# RespiroProject_v0_4.net
KiCad netlist of a schematic drawn in EAGLE
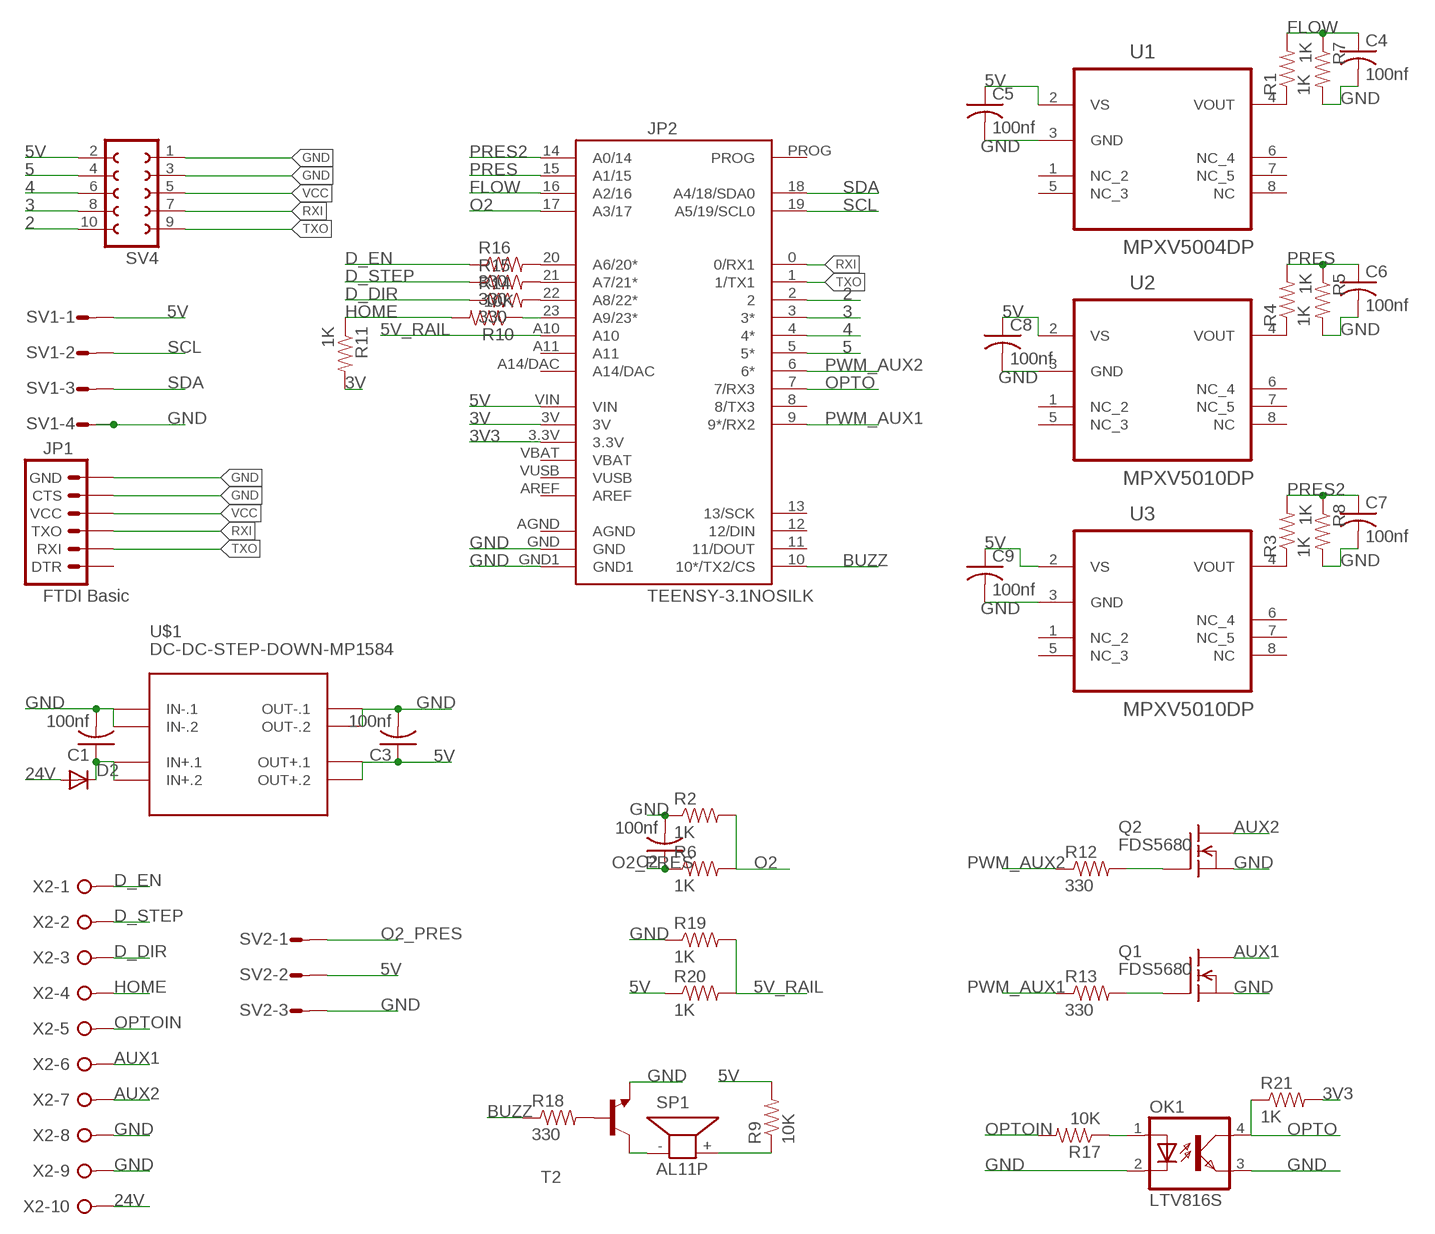
[diagram p0: schematic, sheet 1]

(export (version "E")
  (design (tool "Eeschema 10.0.6"))
  (components
    (comp (ref "C1")
      (value "100nf")
      (footprint "eagle-import:C0805")
      (libsource (lib "eagle-import") (part "C-USC0805"))
    )
    (comp (ref "C2")
      (value "100nf")
      (footprint "eagle-import:C0805")
      (libsource (lib "eagle-import") (part "C-USC0805"))
    )
    (comp (ref "C3")
      (value "100nf")
      (footprint "eagle-import:C0805")
      (libsource (lib "eagle-import") (part "C-USC0805"))
    )
    (comp (ref "C4")
      (value "100nf")
      (footprint "eagle-import:C0805")
      (libsource (lib "eagle-import") (part "C-USC0805"))
    )
    (comp (ref "C5")
      (value "100nf")
      (footprint "eagle-import:C0805")
      (libsource (lib "eagle-import") (part "C-USC0805"))
    )
    (comp (ref "C6")
      (value "100nf")
      (footprint "eagle-import:C0805")
      (libsource (lib "eagle-import") (part "C-USC0805"))
    )
    (comp (ref "C7")
      (value "100nf")
      (footprint "eagle-import:C0805")
      (libsource (lib "eagle-import") (part "C-USC0805"))
    )
    (comp (ref "C8")
      (value "100nf")
      (footprint "eagle-import:C0805")
      (libsource (lib "eagle-import") (part "C-USC0805"))
    )
    (comp (ref "C9")
      (value "100nf")
      (footprint "eagle-import:C0805")
      (libsource (lib "eagle-import") (part "C-USC0805"))
    )
    (comp (ref "D2")
      (value "DIODE-MINIMELF")
      (footprint "eagle-import:MINIMELF")
      (libsource (lib "eagle-import") (part "DIODE-MINIMELF"))
    )
    (comp (ref "JP1")
      (value "FTDI Basic")
      (footprint "eagle-import:1X06")
      (libsource (lib "eagle-import") (part "ARDUINO_SERIAL_PROGRAMPTH"))
    )
    (comp (ref "JP2")
      (value "TEENSY-3.1NOSILK")
      (footprint "eagle-import:TEENSY-3.1_NOSILK")
      (libsource (lib "eagle-import") (part "TEENSY-3.1NOSILK"))
    )
    (comp (ref "OK1")
      (value "LTV816S")
      (footprint "eagle-import:DIL4-SMD")
      (libsource (lib "eagle-import") (part "LTV816S"))
    )
    (comp (ref "Q1")
      (value "FDS5680")
      (footprint "eagle-import:SO-8")
      (libsource (lib "eagle-import") (part "FDS5680"))
    )
    (comp (ref "Q2")
      (value "FDS5680")
      (footprint "eagle-import:SO-8")
      (libsource (lib "eagle-import") (part "FDS5680"))
    )
    (comp (ref "R1")
      (value "1K")
      (footprint "eagle-import:0805")
      (libsource (lib "eagle-import") (part "RESISTOR0805-RES"))
    )
    (comp (ref "R2")
      (value "1K")
      (footprint "eagle-import:0805")
      (libsource (lib "eagle-import") (part "RESISTOR0805-RES"))
    )
    (comp (ref "R3")
      (value "1K")
      (footprint "eagle-import:0805")
      (libsource (lib "eagle-import") (part "RESISTOR0805-RES"))
    )
    (comp (ref "R4")
      (value "1K")
      (footprint "eagle-import:0805")
      (libsource (lib "eagle-import") (part "RESISTOR0805-RES"))
    )
    (comp (ref "R5")
      (value "1K")
      (footprint "eagle-import:0805")
      (libsource (lib "eagle-import") (part "RESISTOR0805-RES"))
    )
    (comp (ref "R6")
      (value "1K")
      (footprint "eagle-import:0805")
      (libsource (lib "eagle-import") (part "RESISTOR0805-RES"))
    )
    (comp (ref "R7")
      (value "1K")
      (footprint "eagle-import:0805")
      (libsource (lib "eagle-import") (part "RESISTOR0805-RES"))
    )
    (comp (ref "R8")
      (value "1K")
      (footprint "eagle-import:0805")
      (libsource (lib "eagle-import") (part "RESISTOR0805-RES"))
    )
    (comp (ref "R9")
      (value "10K")
      (footprint "eagle-import:0805")
      (libsource (lib "eagle-import") (part "RESISTOR0805-RES"))
    )
    (comp (ref "R10")
      (value "10K")
      (footprint "eagle-import:0805")
      (libsource (lib "eagle-import") (part "RESISTOR0805-RES"))
    )
    (comp (ref "R11")
      (value "1K")
      (footprint "eagle-import:0805")
      (libsource (lib "eagle-import") (part "RESISTOR0805-RES"))
    )
    (comp (ref "R12")
      (value "330")
      (footprint "eagle-import:0805")
      (libsource (lib "eagle-import") (part "RESISTOR0805-RES"))
    )
    (comp (ref "R13")
      (value "330")
      (footprint "eagle-import:0805")
      (libsource (lib "eagle-import") (part "RESISTOR0805-RES"))
    )
    (comp (ref "R14")
      (value "330")
      (footprint "eagle-import:0805")
      (libsource (lib "eagle-import") (part "RESISTOR0805-RES"))
    )
    (comp (ref "R15")
      (value "330")
      (footprint "eagle-import:0805")
      (libsource (lib "eagle-import") (part "RESISTOR0805-RES"))
    )
    (comp (ref "R16")
      (value "330")
      (footprint "eagle-import:0805")
      (libsource (lib "eagle-import") (part "RESISTOR0805-RES"))
    )
    (comp (ref "R17")
      (value "10K")
      (footprint "eagle-import:0805")
      (libsource (lib "eagle-import") (part "RESISTOR0805-RES"))
    )
    (comp (ref "R18")
      (value "330")
      (footprint "eagle-import:0805")
      (libsource (lib "eagle-import") (part "RESISTOR0805-RES"))
    )
    (comp (ref "R19")
      (value "1K")
      (footprint "eagle-import:0805")
      (libsource (lib "eagle-import") (part "RESISTOR0805-RES"))
    )
    (comp (ref "R20")
      (value "1K")
      (footprint "eagle-import:0805")
      (libsource (lib "eagle-import") (part "RESISTOR0805-RES"))
    )
    (comp (ref "R21")
      (value "1K")
      (footprint "eagle-import:0805")
      (libsource (lib "eagle-import") (part "RESISTOR0805-RES"))
    )
    (comp (ref "SP1")
      (value "AL11P")
      (footprint "eagle-import:AL11P")
      (libsource (lib "eagle-import") (part "AL11P"))
    )
    (comp (ref "SV1")
      (value "S04P")
      (footprint "eagle-import:S04P")
      (libsource (lib "eagle-import") (part "S04P"))
    )
    (comp (ref "SV2")
      (value "S03P")
      (footprint "eagle-import:S03P")
      (libsource (lib "eagle-import") (part "S03P"))
    )
    (comp (ref "SV4")
      (value "FE05-2")
      (footprint "eagle-import:FE05-2")
      (libsource (lib "eagle-import") (part "FE05-2"))
    )
    (comp (ref "T2")
      (value "BC817-16-NPN-SOT23-BEC")
      (footprint "eagle-import:SOT23-BEC")
      (libsource (lib "eagle-import") (part "-NPN-SOT23-BECBC817-16"))
    )
    (comp (ref "U$1")
      (value "DC-DC-STEP-DOWN-MP1584")
      (footprint "eagle-import:DC-DC-STEP-DOWN-MP1584")
      (libsource (lib "eagle-import") (part "DC-DC-STEP-DOWN-MP1584"))
    )
    (comp (ref "U1")
      (value "MPXV5004DP")
      (footprint "eagle-import:FREESCALE_CASE_1351-01")
      (libsource (lib "eagle-import") (part "MPXV5004DP"))
    )
    (comp (ref "U2")
      (value "MPXV5010DP")
      (footprint "eagle-import:FREESCALE_CASE_1351-01")
      (fields (field (name "MPN") "MPXV5004DP"))
      (libsource (lib "eagle-import") (part "MPXV5004DP"))
    )
    (comp (ref "U3")
      (value "MPXV5010DP")
      (footprint "eagle-import:FREESCALE_CASE_1351-01")
      (fields (field (name "MPN") "MPXV5004DP"))
      (libsource (lib "eagle-import") (part "MPXV5004DP"))
    )
    (comp (ref "X2")
      (value "W237-10P")
      (footprint "eagle-import:W237-10P")
      (libsource (lib "eagle-import") (part "W237-10P"))
    )
  )
  (nets
    (net (code "1") (name "/2") (class "Default")
      (node (ref "JP2") (pin "2") (pinfunction "2_2") (pintype "bidirectional"))
      (node (ref "SV4") (pin "10") (pinfunction "10_10") (pintype "passive"))
    )
    (net (code "2") (name "/3") (class "Default")
      (node (ref "JP2") (pin "3") (pinfunction "3*_3") (pintype "bidirectional"))
      (node (ref "SV4") (pin "8") (pinfunction "8_8") (pintype "passive"))
    )
    (net (code "3") (name "/3V") (class "Default")
      (node (ref "JP2") (pin "3V") (pinfunction "3V_3V") (pintype "bidirectional"))
      (node (ref "R11") (pin "2") (pinfunction "2_2") (pintype "passive"))
    )
    (net (code "4") (name "/3V3") (class "Default")
      (node (ref "JP2") (pin "3.3V") (pinfunction "3.3V_3.3V") (pintype "bidirectional"))
      (node (ref "R21") (pin "2") (pinfunction "2_2") (pintype "passive"))
    )
    (net (code "5") (name "/4") (class "Default")
      (node (ref "JP2") (pin "4") (pinfunction "4*_4") (pintype "bidirectional"))
      (node (ref "SV4") (pin "6") (pinfunction "6_6") (pintype "passive"))
    )
    (net (code "6") (name "/5") (class "Default")
      (node (ref "JP2") (pin "5") (pinfunction "5*_5") (pintype "bidirectional"))
      (node (ref "SV4") (pin "4") (pinfunction "4_4") (pintype "passive"))
    )
    (net (code "7") (name "/5V") (class "Default")
      (node (ref "C3") (pin "1") (pinfunction "1_1") (pintype "passive"))
      (node (ref "C5") (pin "1") (pinfunction "1_1") (pintype "passive"))
      (node (ref "C8") (pin "1") (pinfunction "1_1") (pintype "passive"))
      (node (ref "C9") (pin "1") (pinfunction "1_1") (pintype "passive"))
      (node (ref "JP2") (pin "VIN") (pinfunction "VIN_VIN") (pintype "bidirectional"))
      (node (ref "R20") (pin "1") (pinfunction "1_1") (pintype "passive"))
      (node (ref "R9") (pin "2") (pinfunction "2_2") (pintype "passive"))
      (node (ref "SV1") (pin "1") (pinfunction "S_1") (pintype "passive"))
      (node (ref "SV2") (pin "2") (pinfunction "S_2") (pintype "passive"))
      (node (ref "SV4") (pin "2") (pinfunction "2_2") (pintype "passive"))
      (node (ref "U$1") (pin "OUT+.1") (pinfunction "OUT+.1_OUT+.1") (pintype "bidirectional"))
      (node (ref "U$1") (pin "OUT+.2") (pinfunction "OUT+.2_OUT+.2") (pintype "bidirectional"))
      (node (ref "U1") (pin "2") (pinfunction "VS_2") (pintype "power_in"))
      (node (ref "U2") (pin "2") (pinfunction "VS_2") (pintype "power_in"))
      (node (ref "U3") (pin "2") (pinfunction "VS_2") (pintype "power_in"))
    )
    (net (code "8") (name "/5V_RAIL") (class "Default")
      (node (ref "JP2") (pin "A10") (pinfunction "A10_A10") (pintype "bidirectional"))
      (node (ref "R19") (pin "2") (pinfunction "2_2") (pintype "passive"))
      (node (ref "R20") (pin "2") (pinfunction "2_2") (pintype "passive"))
    )
    (net (code "9") (name "/24V") (class "Default")
      (node (ref "D2") (pin "A") (pinfunction "A_A") (pintype "passive"))
      (node (ref "X2") (pin "10") (pinfunction "KL_10") (pintype "passive"))
    )
    (net (code "10") (name "/AUX1") (class "Default")
      (node (ref "Q1") (pin "5") (pinfunction "D_5") (pintype "passive"))
      (node (ref "Q1") (pin "6") (pinfunction "D_6") (pintype "passive"))
      (node (ref "Q1") (pin "7") (pinfunction "D_7") (pintype "passive"))
      (node (ref "Q1") (pin "8") (pinfunction "D_8") (pintype "passive"))
      (node (ref "X2") (pin "6") (pinfunction "KL_6") (pintype "passive"))
    )
    (net (code "11") (name "/AUX2") (class "Default")
      (node (ref "Q2") (pin "5") (pinfunction "D_5") (pintype "passive"))
      (node (ref "Q2") (pin "6") (pinfunction "D_6") (pintype "passive"))
      (node (ref "Q2") (pin "7") (pinfunction "D_7") (pintype "passive"))
      (node (ref "Q2") (pin "8") (pinfunction "D_8") (pintype "passive"))
      (node (ref "X2") (pin "7") (pinfunction "KL_7") (pintype "passive"))
    )
    (net (code "12") (name "/BUZZ") (class "Default")
      (node (ref "JP2") (pin "10") (pinfunction "10*/TX2/CS_10") (pintype "bidirectional"))
      (node (ref "R18") (pin "1") (pinfunction "1_1") (pintype "passive"))
    )
    (net (code "13") (name "/D_DIR") (class "Default")
      (node (ref "R14") (pin "1") (pinfunction "1_1") (pintype "passive"))
      (node (ref "X2") (pin "3") (pinfunction "KL_3") (pintype "passive"))
    )
    (net (code "14") (name "/D_EN") (class "Default")
      (node (ref "R16") (pin "1") (pinfunction "1_1") (pintype "passive"))
      (node (ref "X2") (pin "1") (pinfunction "KL_1") (pintype "passive"))
    )
    (net (code "15") (name "/D_STEP") (class "Default")
      (node (ref "R15") (pin "1") (pinfunction "1_1") (pintype "passive"))
      (node (ref "X2") (pin "2") (pinfunction "KL_2") (pintype "passive"))
    )
    (net (code "16") (name "/FLOW") (class "Default")
      (node (ref "C4") (pin "1") (pinfunction "1_1") (pintype "passive"))
      (node (ref "JP2") (pin "16") (pinfunction "A2/16_16") (pintype "bidirectional"))
      (node (ref "R1") (pin "2") (pinfunction "2_2") (pintype "passive"))
      (node (ref "R7") (pin "1") (pinfunction "1_1") (pintype "passive"))
    )
    (net (code "17") (name "/HOME") (class "Default")
      (node (ref "R10") (pin "2") (pinfunction "2_2") (pintype "passive"))
      (node (ref "R11") (pin "1") (pinfunction "1_1") (pintype "passive"))
      (node (ref "X2") (pin "4") (pinfunction "KL_4") (pintype "passive"))
    )
    (net (code "18") (name "/O2") (class "Default")
      (node (ref "JP2") (pin "17") (pinfunction "A3/17_17") (pintype "bidirectional"))
      (node (ref "R2") (pin "2") (pinfunction "2_2") (pintype "passive"))
      (node (ref "R6") (pin "2") (pinfunction "2_2") (pintype "passive"))
    )
    (net (code "19") (name "/O2_PRES") (class "Default")
      (node (ref "C2") (pin "1") (pinfunction "1_1") (pintype "passive"))
      (node (ref "R6") (pin "1") (pinfunction "1_1") (pintype "passive"))
      (node (ref "SV2") (pin "1") (pinfunction "S_1") (pintype "passive"))
    )
    (net (code "20") (name "/OPTO") (class "Default")
      (node (ref "JP2") (pin "7") (pinfunction "7/RX3_7") (pintype "bidirectional"))
      (node (ref "OK1") (pin "4") (pinfunction "COL_4") (pintype "passive"))
      (node (ref "R21") (pin "1") (pinfunction "1_1") (pintype "passive"))
    )
    (net (code "21") (name "/OPTOIN") (class "Default")
      (node (ref "R17") (pin "2") (pinfunction "2_2") (pintype "passive"))
      (node (ref "X2") (pin "5") (pinfunction "KL_5") (pintype "passive"))
    )
    (net (code "22") (name "/PRES") (class "Default")
      (node (ref "C6") (pin "1") (pinfunction "1_1") (pintype "passive"))
      (node (ref "JP2") (pin "15") (pinfunction "A1/15_15") (pintype "bidirectional"))
      (node (ref "R4") (pin "2") (pinfunction "2_2") (pintype "passive"))
      (node (ref "R5") (pin "1") (pinfunction "1_1") (pintype "passive"))
    )
    (net (code "23") (name "/PRES2") (class "Default")
      (node (ref "C7") (pin "1") (pinfunction "1_1") (pintype "passive"))
      (node (ref "JP2") (pin "14") (pinfunction "A0/14_14") (pintype "bidirectional"))
      (node (ref "R3") (pin "2") (pinfunction "2_2") (pintype "passive"))
      (node (ref "R8") (pin "1") (pinfunction "1_1") (pintype "passive"))
    )
    (net (code "24") (name "/PWM_AUX1") (class "Default")
      (node (ref "JP2") (pin "9") (pinfunction "9*/RX2_9") (pintype "bidirectional"))
      (node (ref "R13") (pin "1") (pinfunction "1_1") (pintype "passive"))
    )
    (net (code "25") (name "/PWM_AUX2") (class "Default")
      (node (ref "JP2") (pin "6") (pinfunction "6*_6") (pintype "bidirectional"))
      (node (ref "R12") (pin "1") (pinfunction "1_1") (pintype "passive"))
    )
    (net (code "26") (name "/SCL") (class "Default")
      (node (ref "JP2") (pin "19") (pinfunction "A5/19/SCL0_19") (pintype "bidirectional"))
      (node (ref "SV1") (pin "2") (pinfunction "S_2") (pintype "passive"))
    )
    (net (code "27") (name "/SDA") (class "Default")
      (node (ref "JP2") (pin "18") (pinfunction "A4/18/SDA0_18") (pintype "bidirectional"))
      (node (ref "SV1") (pin "3") (pinfunction "S_3") (pintype "passive"))
    )
    (net (code "28") (name "GND") (class "Default")
      (node (ref "C1") (pin "2") (pinfunction "2_2") (pintype "passive"))
      (node (ref "C2") (pin "2") (pinfunction "2_2") (pintype "passive"))
      (node (ref "C3") (pin "2") (pinfunction "2_2") (pintype "passive"))
      (node (ref "C4") (pin "2") (pinfunction "2_2") (pintype "passive"))
      (node (ref "C5") (pin "2") (pinfunction "2_2") (pintype "passive"))
      (node (ref "C6") (pin "2") (pinfunction "2_2") (pintype "passive"))
      (node (ref "C7") (pin "2") (pinfunction "2_2") (pintype "passive"))
      (node (ref "C8") (pin "2") (pinfunction "2_2") (pintype "passive"))
      (node (ref "C9") (pin "2") (pinfunction "2_2") (pintype "passive"))
      (node (ref "JP1") (pin "5") (pinfunction "CTS_5") (pintype "passive"))
      (node (ref "JP1") (pin "6") (pinfunction "GND_6") (pintype "passive"))
      (node (ref "JP2") (pin "GND") (pinfunction "GND_GND") (pintype "bidirectional"))
      (node (ref "JP2") (pin "GND1") (pinfunction "GND1_GND1") (pintype "bidirectional"))
      (node (ref "OK1") (pin "2") (pinfunction "C_2") (pintype "passive"))
      (node (ref "OK1") (pin "3") (pinfunction "EMIT_3") (pintype "passive"))
      (node (ref "Q1") (pin "1") (pinfunction "S_1") (pintype "passive"))
      (node (ref "Q1") (pin "2") (pinfunction "S_2") (pintype "passive"))
      (node (ref "Q1") (pin "3") (pinfunction "S_3") (pintype "passive"))
      (node (ref "Q2") (pin "1") (pinfunction "S_1") (pintype "passive"))
      (node (ref "Q2") (pin "2") (pinfunction "S_2") (pintype "passive"))
      (node (ref "Q2") (pin "3") (pinfunction "S_3") (pintype "passive"))
      (node (ref "R19") (pin "1") (pinfunction "1_1") (pintype "passive"))
      (node (ref "R2") (pin "1") (pinfunction "1_1") (pintype "passive"))
      (node (ref "R5") (pin "2") (pinfunction "2_2") (pintype "passive"))
      (node (ref "R7") (pin "2") (pinfunction "2_2") (pintype "passive"))
      (node (ref "R8") (pin "2") (pinfunction "2_2") (pintype "passive"))
      (node (ref "SV1") (pin "4") (pinfunction "S_4") (pintype "passive"))
      (node (ref "SV2") (pin "3") (pinfunction "S_3") (pintype "passive"))
      (node (ref "SV4") (pin "1") (pinfunction "1_1") (pintype "passive"))
      (node (ref "SV4") (pin "3") (pinfunction "3_3") (pintype "passive"))
      (node (ref "T2") (pin "E") (pinfunction "E_E") (pintype "passive"))
      (node (ref "U$1") (pin "IN-.1") (pinfunction "IN-.1_IN-.1") (pintype "bidirectional"))
      (node (ref "U$1") (pin "IN-.2") (pinfunction "IN-.2_IN-.2") (pintype "bidirectional"))
      (node (ref "U$1") (pin "OUT-.1") (pinfunction "OUT-.1_OUT-.1") (pintype "bidirectional"))
      (node (ref "U$1") (pin "OUT-.2") (pinfunction "OUT-.2_OUT-.2") (pintype "bidirectional"))
      (node (ref "U1") (pin "3") (pinfunction "GND_3") (pintype "power_in"))
      (node (ref "U2") (pin "3") (pinfunction "GND_3") (pintype "power_in"))
      (node (ref "U3") (pin "3") (pinfunction "GND_3") (pintype "power_in"))
      (node (ref "X2") (pin "8") (pinfunction "KL_8") (pintype "passive"))
      (node (ref "X2") (pin "9") (pinfunction "KL_9") (pintype "passive"))
    )
    (net (code "29") (name "Net-(C1-Pad1)") (class "Default")
      (node (ref "C1") (pin "1") (pinfunction "1_1") (pintype "passive"))
      (node (ref "D2") (pin "C") (pinfunction "C_C") (pintype "passive"))
      (node (ref "U$1") (pin "IN+.1") (pinfunction "IN+.1_IN+.1") (pintype "bidirectional"))
      (node (ref "U$1") (pin "IN+.2") (pinfunction "IN+.2_IN+.2") (pintype "bidirectional"))
    )
    (net (code "30") (name "Net-(JP2-A6{slash}20*)") (class "Default")
      (node (ref "JP2") (pin "20") (pinfunction "A6/20*_20") (pintype "bidirectional"))
      (node (ref "R16") (pin "2") (pinfunction "2_2") (pintype "passive"))
    )
    (net (code "31") (name "Net-(JP2-A7{slash}21*)") (class "Default")
      (node (ref "JP2") (pin "21") (pinfunction "A7/21*_21") (pintype "bidirectional"))
      (node (ref "R15") (pin "2") (pinfunction "2_2") (pintype "passive"))
    )
    (net (code "32") (name "Net-(JP2-A8{slash}22*)") (class "Default")
      (node (ref "JP2") (pin "22") (pinfunction "A8/22*_22") (pintype "bidirectional"))
      (node (ref "R14") (pin "2") (pinfunction "2_2") (pintype "passive"))
    )
    (net (code "33") (name "Net-(JP2-A9{slash}23*)") (class "Default")
      (node (ref "JP2") (pin "23") (pinfunction "A9/23*_23") (pintype "bidirectional"))
      (node (ref "R10") (pin "1") (pinfunction "1_1") (pintype "passive"))
    )
    (net (code "34") (name "Net-(OK1-A)") (class "Default")
      (node (ref "OK1") (pin "1") (pinfunction "A_1") (pintype "passive"))
      (node (ref "R17") (pin "1") (pinfunction "1_1") (pintype "passive"))
    )
    (net (code "35") (name "Net-(Q1-G)") (class "Default")
      (node (ref "Q1") (pin "4") (pinfunction "G_4") (pintype "passive"))
      (node (ref "R13") (pin "2") (pinfunction "2_2") (pintype "passive"))
    )
    (net (code "36") (name "Net-(Q2-G)") (class "Default")
      (node (ref "Q2") (pin "4") (pinfunction "G_4") (pintype "passive"))
      (node (ref "R12") (pin "2") (pinfunction "2_2") (pintype "passive"))
    )
    (net (code "37") (name "Net-(R18-Pad2)") (class "Default")
      (node (ref "R18") (pin "2") (pinfunction "2_2") (pintype "passive"))
      (node (ref "T2") (pin "B") (pinfunction "B_B") (pintype "passive"))
    )
    (net (code "38") (name "Net-(SP1-1)") (class "Default")
      (node (ref "SP1") (pin "-") (pinfunction "1_-") (pintype "passive"))
      (node (ref "T2") (pin "C") (pinfunction "C_C") (pintype "passive"))
    )
    (net (code "39") (name "Net-(SP1-2)") (class "Default")
      (node (ref "R9") (pin "1") (pinfunction "1_1") (pintype "passive"))
      (node (ref "SP1") (pin "+") (pinfunction "2_+") (pintype "passive"))
    )
    (net (code "40") (name "Net-(U1-VOUT)") (class "Default")
      (node (ref "R1") (pin "1") (pinfunction "1_1") (pintype "passive"))
      (node (ref "U1") (pin "4") (pinfunction "VOUT_4") (pintype "output"))
    )
    (net (code "41") (name "Net-(U2-VOUT)") (class "Default")
      (node (ref "R4") (pin "1") (pinfunction "1_1") (pintype "passive"))
      (node (ref "U2") (pin "4") (pinfunction "VOUT_4") (pintype "output"))
    )
    (net (code "42") (name "Net-(U3-VOUT)") (class "Default")
      (node (ref "R3") (pin "1") (pinfunction "1_1") (pintype "passive"))
      (node (ref "U3") (pin "4") (pinfunction "VOUT_4") (pintype "output"))
    )
    (net (code "43") (name "RXI") (class "Default")
      (node (ref "JP1") (pin "3") (pinfunction "TXO_3") (pintype "passive"))
      (node (ref "JP2") (pin "0") (pinfunction "0/RX1_0") (pintype "bidirectional"))
      (node (ref "SV4") (pin "7") (pinfunction "7_7") (pintype "passive"))
    )
    (net (code "44") (name "TXO") (class "Default")
      (node (ref "JP1") (pin "2") (pinfunction "RXI_2") (pintype "passive"))
      (node (ref "JP2") (pin "1") (pinfunction "1/TX1_1") (pintype "bidirectional"))
      (node (ref "SV4") (pin "9") (pinfunction "9_9") (pintype "passive"))
    )
    (net (code "45") (name "VCC") (class "Default")
      (node (ref "JP1") (pin "4") (pinfunction "VCC_4") (pintype "passive"))
      (node (ref "SV4") (pin "5") (pinfunction "5_5") (pintype "passive"))
    )
    (net (code "46") (name "unconnected-(JP1-DTR-Pad1)") (class "Default")
      (node (ref "JP1") (pin "1") (pinfunction "DTR_1") (pintype "passive"))
    )
    (net (code "47") (name "unconnected-(JP2-8{slash}TX3-Pad8)") (class "Default")
      (node (ref "JP2") (pin "8") (pinfunction "8/TX3_8") (pintype "bidirectional"))
    )
    (net (code "48") (name "unconnected-(JP2-11{slash}DOUT-Pad11)") (class "Default")
      (node (ref "JP2") (pin "11") (pinfunction "11/DOUT_11") (pintype "bidirectional"))
    )
    (net (code "49") (name "unconnected-(JP2-12{slash}DIN-Pad12)") (class "Default")
      (node (ref "JP2") (pin "12") (pinfunction "12/DIN_12") (pintype "bidirectional"))
    )
    (net (code "50") (name "unconnected-(JP2-13{slash}SCK-Pad13)") (class "Default")
      (node (ref "JP2") (pin "13") (pinfunction "13/SCK_13") (pintype "bidirectional"))
    )
    (net (code "51") (name "unconnected-(JP2-PadA11)") (class "Default")
      (node (ref "JP2") (pin "A11") (pinfunction "A11_A11") (pintype "bidirectional"))
    )
    (net (code "52") (name "unconnected-(JP2-PadA14{slash}DAC)") (class "Default")
      (node (ref "JP2") (pin "A14/DAC") (pinfunction "A14/DAC_A14/DAC") (pintype "bidirectional"))
    )
    (net (code "53") (name "unconnected-(JP2-PadAGND)") (class "Default")
      (node (ref "JP2") (pin "AGND") (pinfunction "AGND_AGND") (pintype "bidirectional"))
    )
    (net (code "54") (name "unconnected-(JP2-PadAREF)") (class "Default")
      (node (ref "JP2") (pin "AREF") (pinfunction "AREF_AREF") (pintype "bidirectional"))
    )
    (net (code "55") (name "unconnected-(JP2-PadPROG)") (class "Default")
      (node (ref "JP2") (pin "PROG") (pinfunction "PROG_PROG") (pintype "bidirectional"))
    )
    (net (code "56") (name "unconnected-(JP2-PadVBAT)") (class "Default")
      (node (ref "JP2") (pin "VBAT") (pinfunction "VBAT_VBAT") (pintype "bidirectional"))
    )
    (net (code "57") (name "unconnected-(JP2-PadVUSB)") (class "Default")
      (node (ref "JP2") (pin "VUSB") (pinfunction "VUSB_VUSB") (pintype "bidirectional"))
    )
    (net (code "58") (name "unconnected-(U1-NC-Pad8)") (class "Default")
      (node (ref "U1") (pin "8") (pinfunction "NC_8") (pintype "no_connect"))
    )
    (net (code "59") (name "unconnected-(U1-NC_2-Pad1)") (class "Default")
      (node (ref "U1") (pin "1") (pinfunction "NC_2_1") (pintype "no_connect"))
    )
    (net (code "60") (name "unconnected-(U1-NC_3-Pad5)") (class "Default")
      (node (ref "U1") (pin "5") (pinfunction "NC_3_5") (pintype "no_connect"))
    )
    (net (code "61") (name "unconnected-(U1-NC_4-Pad6)") (class "Default")
      (node (ref "U1") (pin "6") (pinfunction "NC_4_6") (pintype "no_connect"))
    )
    (net (code "62") (name "unconnected-(U1-NC_5-Pad7)") (class "Default")
      (node (ref "U1") (pin "7") (pinfunction "NC_5_7") (pintype "no_connect"))
    )
    (net (code "63") (name "unconnected-(U2-NC-Pad8)") (class "Default")
      (node (ref "U2") (pin "8") (pinfunction "NC_8") (pintype "no_connect"))
    )
    (net (code "64") (name "unconnected-(U2-NC_2-Pad1)") (class "Default")
      (node (ref "U2") (pin "1") (pinfunction "NC_2_1") (pintype "no_connect"))
    )
    (net (code "65") (name "unconnected-(U2-NC_3-Pad5)") (class "Default")
      (node (ref "U2") (pin "5") (pinfunction "NC_3_5") (pintype "no_connect"))
    )
    (net (code "66") (name "unconnected-(U2-NC_4-Pad6)") (class "Default")
      (node (ref "U2") (pin "6") (pinfunction "NC_4_6") (pintype "no_connect"))
    )
    (net (code "67") (name "unconnected-(U2-NC_5-Pad7)") (class "Default")
      (node (ref "U2") (pin "7") (pinfunction "NC_5_7") (pintype "no_connect"))
    )
    (net (code "68") (name "unconnected-(U3-NC-Pad8)") (class "Default")
      (node (ref "U3") (pin "8") (pinfunction "NC_8") (pintype "no_connect"))
    )
    (net (code "69") (name "unconnected-(U3-NC_2-Pad1)") (class "Default")
      (node (ref "U3") (pin "1") (pinfunction "NC_2_1") (pintype "no_connect"))
    )
    (net (code "70") (name "unconnected-(U3-NC_3-Pad5)") (class "Default")
      (node (ref "U3") (pin "5") (pinfunction "NC_3_5") (pintype "no_connect"))
    )
    (net (code "71") (name "unconnected-(U3-NC_4-Pad6)") (class "Default")
      (node (ref "U3") (pin "6") (pinfunction "NC_4_6") (pintype "no_connect"))
    )
    (net (code "72") (name "unconnected-(U3-NC_5-Pad7)") (class "Default")
      (node (ref "U3") (pin "7") (pinfunction "NC_5_7") (pintype "no_connect"))
    )
  )
)
